# PA.net
KiCad netlist of a schematic drawn in Altium Designer
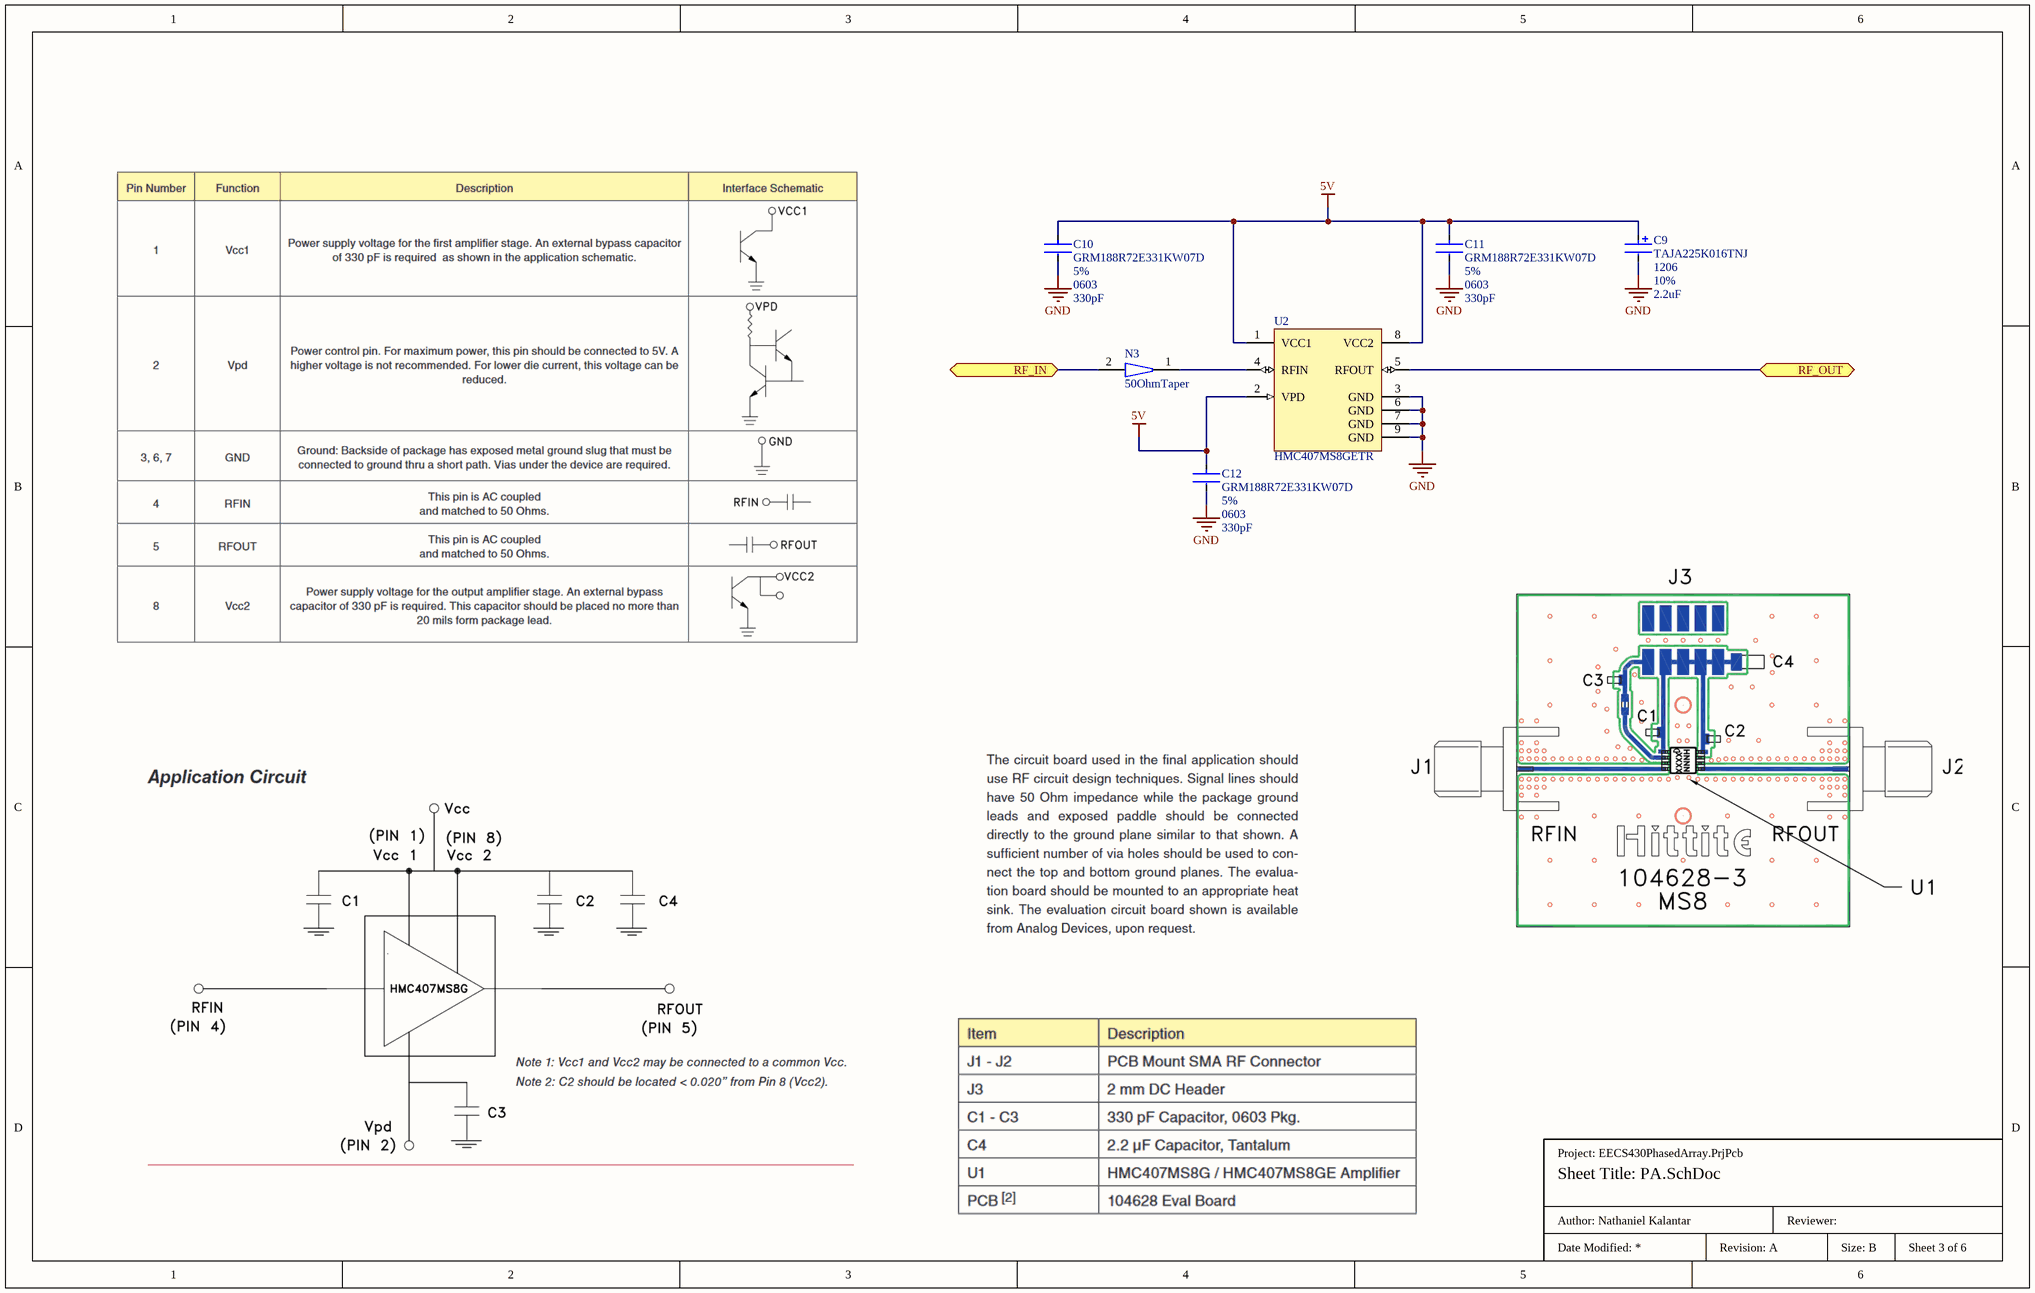
[diagram p0: PA.SchDoc]

(export (version "E")
  (design (tool "Eeschema 10.0.6"))
  (components
    (comp (ref "C9")
      (value "TAJA225K016TNJ")
      (footprint "TantCapKyocera1206")
      (description "2.2 µF Molded Tantalum Capacitors 16 V 1206 (3216 Metric) 6.5Ohm @ 100kHz")
      (fields
        (field (name "MANUFACTURER") "Kyocera AVX")
        (field (name "MANUFACTURER PART NUMBER") "TPSB226K020T0400")
        (field (name "PACKAGE") "1206")
        (field (name "TOLERANCE") "10%")
        (field (name "ALTIUM_VALUE") "2.2uF")
      )
      (libsource (lib "EECS430PhasedArray") (part "TAJA225K016TNJ"))
    )
    (comp (ref "C10")
      (value "GRM188R72E331KW07D")
      (footprint "Murata0603CeramicCap")
      (description "330 pF ±10% 250V Ceramic Capacitor X7R 0603 (1608 Metric)")
      (fields
        (field (name "TOLERANCE") "5%")
        (field (name "PACKAGE") "0603")
        (field (name "ALTIUM_VALUE") "330pF")
      )
      (libsource (lib "EECS430PhasedArray") (part "GRM188R72E331KW07D"))
    )
    (comp (ref "C11")
      (value "GRM188R72E331KW07D")
      (footprint "Murata0603CeramicCap")
      (description "330 pF ±10% 250V Ceramic Capacitor X7R 0603 (1608 Metric)")
      (fields
        (field (name "TOLERANCE") "5%")
        (field (name "PACKAGE") "0603")
        (field (name "ALTIUM_VALUE") "330pF")
      )
      (libsource (lib "EECS430PhasedArray") (part "GRM188R72E331KW07D"))
    )
    (comp (ref "C12")
      (value "GRM188R72E331KW07D")
      (footprint "Murata0603CeramicCap")
      (description "330 pF ±10% 250V Ceramic Capacitor X7R 0603 (1608 Metric)")
      (fields
        (field (name "TOLERANCE") "5%")
        (field (name "PACKAGE") "0603")
        (field (name "ALTIUM_VALUE") "330pF")
      )
      (libsource (lib "EECS430PhasedArray") (part "GRM188R72E331KW07D"))
    )
    (comp (ref "N3")
      (value "50OhmTaper")
      (footprint "50OhmTaper")
      (description "Triangular taper from 50 Ohms to 0402 width")
      (libsource (lib "EECS430PhasedArray") (part "50OhmTaper"))
    )
    (comp (ref "U2")
      (value "HMC407MS8GETR")
      (footprint "HMC407MS8GETR")
      (description "RF Amplifier IC General Purpose 5GHz ~ 7GHz 8-MSOP-EP")
      (libsource (lib "EECS430PhasedArray") (part "HMC407MS8GETR"))
    )
  )
  (nets
    (net (code "1") (name "/RF_IN") (class "Default")
      (node (ref "N3") (pin "2") (pinfunction "2_2") (pintype "passive"))
    )
    (net (code "2") (name "/RF_OUT") (class "Default")
      (node (ref "U2") (pin "5") (pinfunction "RFOUT_5") (pintype "bidirectional"))
    )
    (net (code "3") (name "5V") (class "Default")
      (node (ref "C10") (pin "1") (pinfunction "1_1") (pintype "passive"))
      (node (ref "C11") (pin "1") (pinfunction "1_1") (pintype "passive"))
      (node (ref "C12") (pin "1") (pinfunction "1_1") (pintype "passive"))
      (node (ref "C9") (pin "1") (pinfunction "1_1") (pintype "passive"))
      (node (ref "U2") (pin "1") (pinfunction "VCC1_1") (pintype "power_in"))
      (node (ref "U2") (pin "2") (pinfunction "VPD_2") (pintype "input"))
      (node (ref "U2") (pin "8") (pinfunction "VCC2_8") (pintype "power_in"))
    )
    (net (code "4") (name "GND") (class "Default")
      (node (ref "C10") (pin "2") (pinfunction "2_2") (pintype "passive"))
      (node (ref "C11") (pin "2") (pinfunction "2_2") (pintype "passive"))
      (node (ref "C12") (pin "2") (pinfunction "2_2") (pintype "passive"))
      (node (ref "C9") (pin "2") (pinfunction "2_2") (pintype "passive"))
      (node (ref "U2") (pin "3") (pinfunction "GND_3") (pintype "power_in"))
      (node (ref "U2") (pin "6") (pinfunction "GND_6") (pintype "power_in"))
      (node (ref "U2") (pin "7") (pinfunction "GND_7") (pintype "power_in"))
      (node (ref "U2") (pin "9") (pinfunction "GND_9") (pintype "power_in"))
    )
    (net (code "5") (name "Net-(U2-RFIN)") (class "Default")
      (node (ref "N3") (pin "1") (pinfunction "1_1") (pintype "passive"))
      (node (ref "U2") (pin "4") (pinfunction "RFIN_4") (pintype "bidirectional"))
    )
  )
)
